# 10_10.net
KiCad netlist of a schematic drawn in EasyEDA Pro
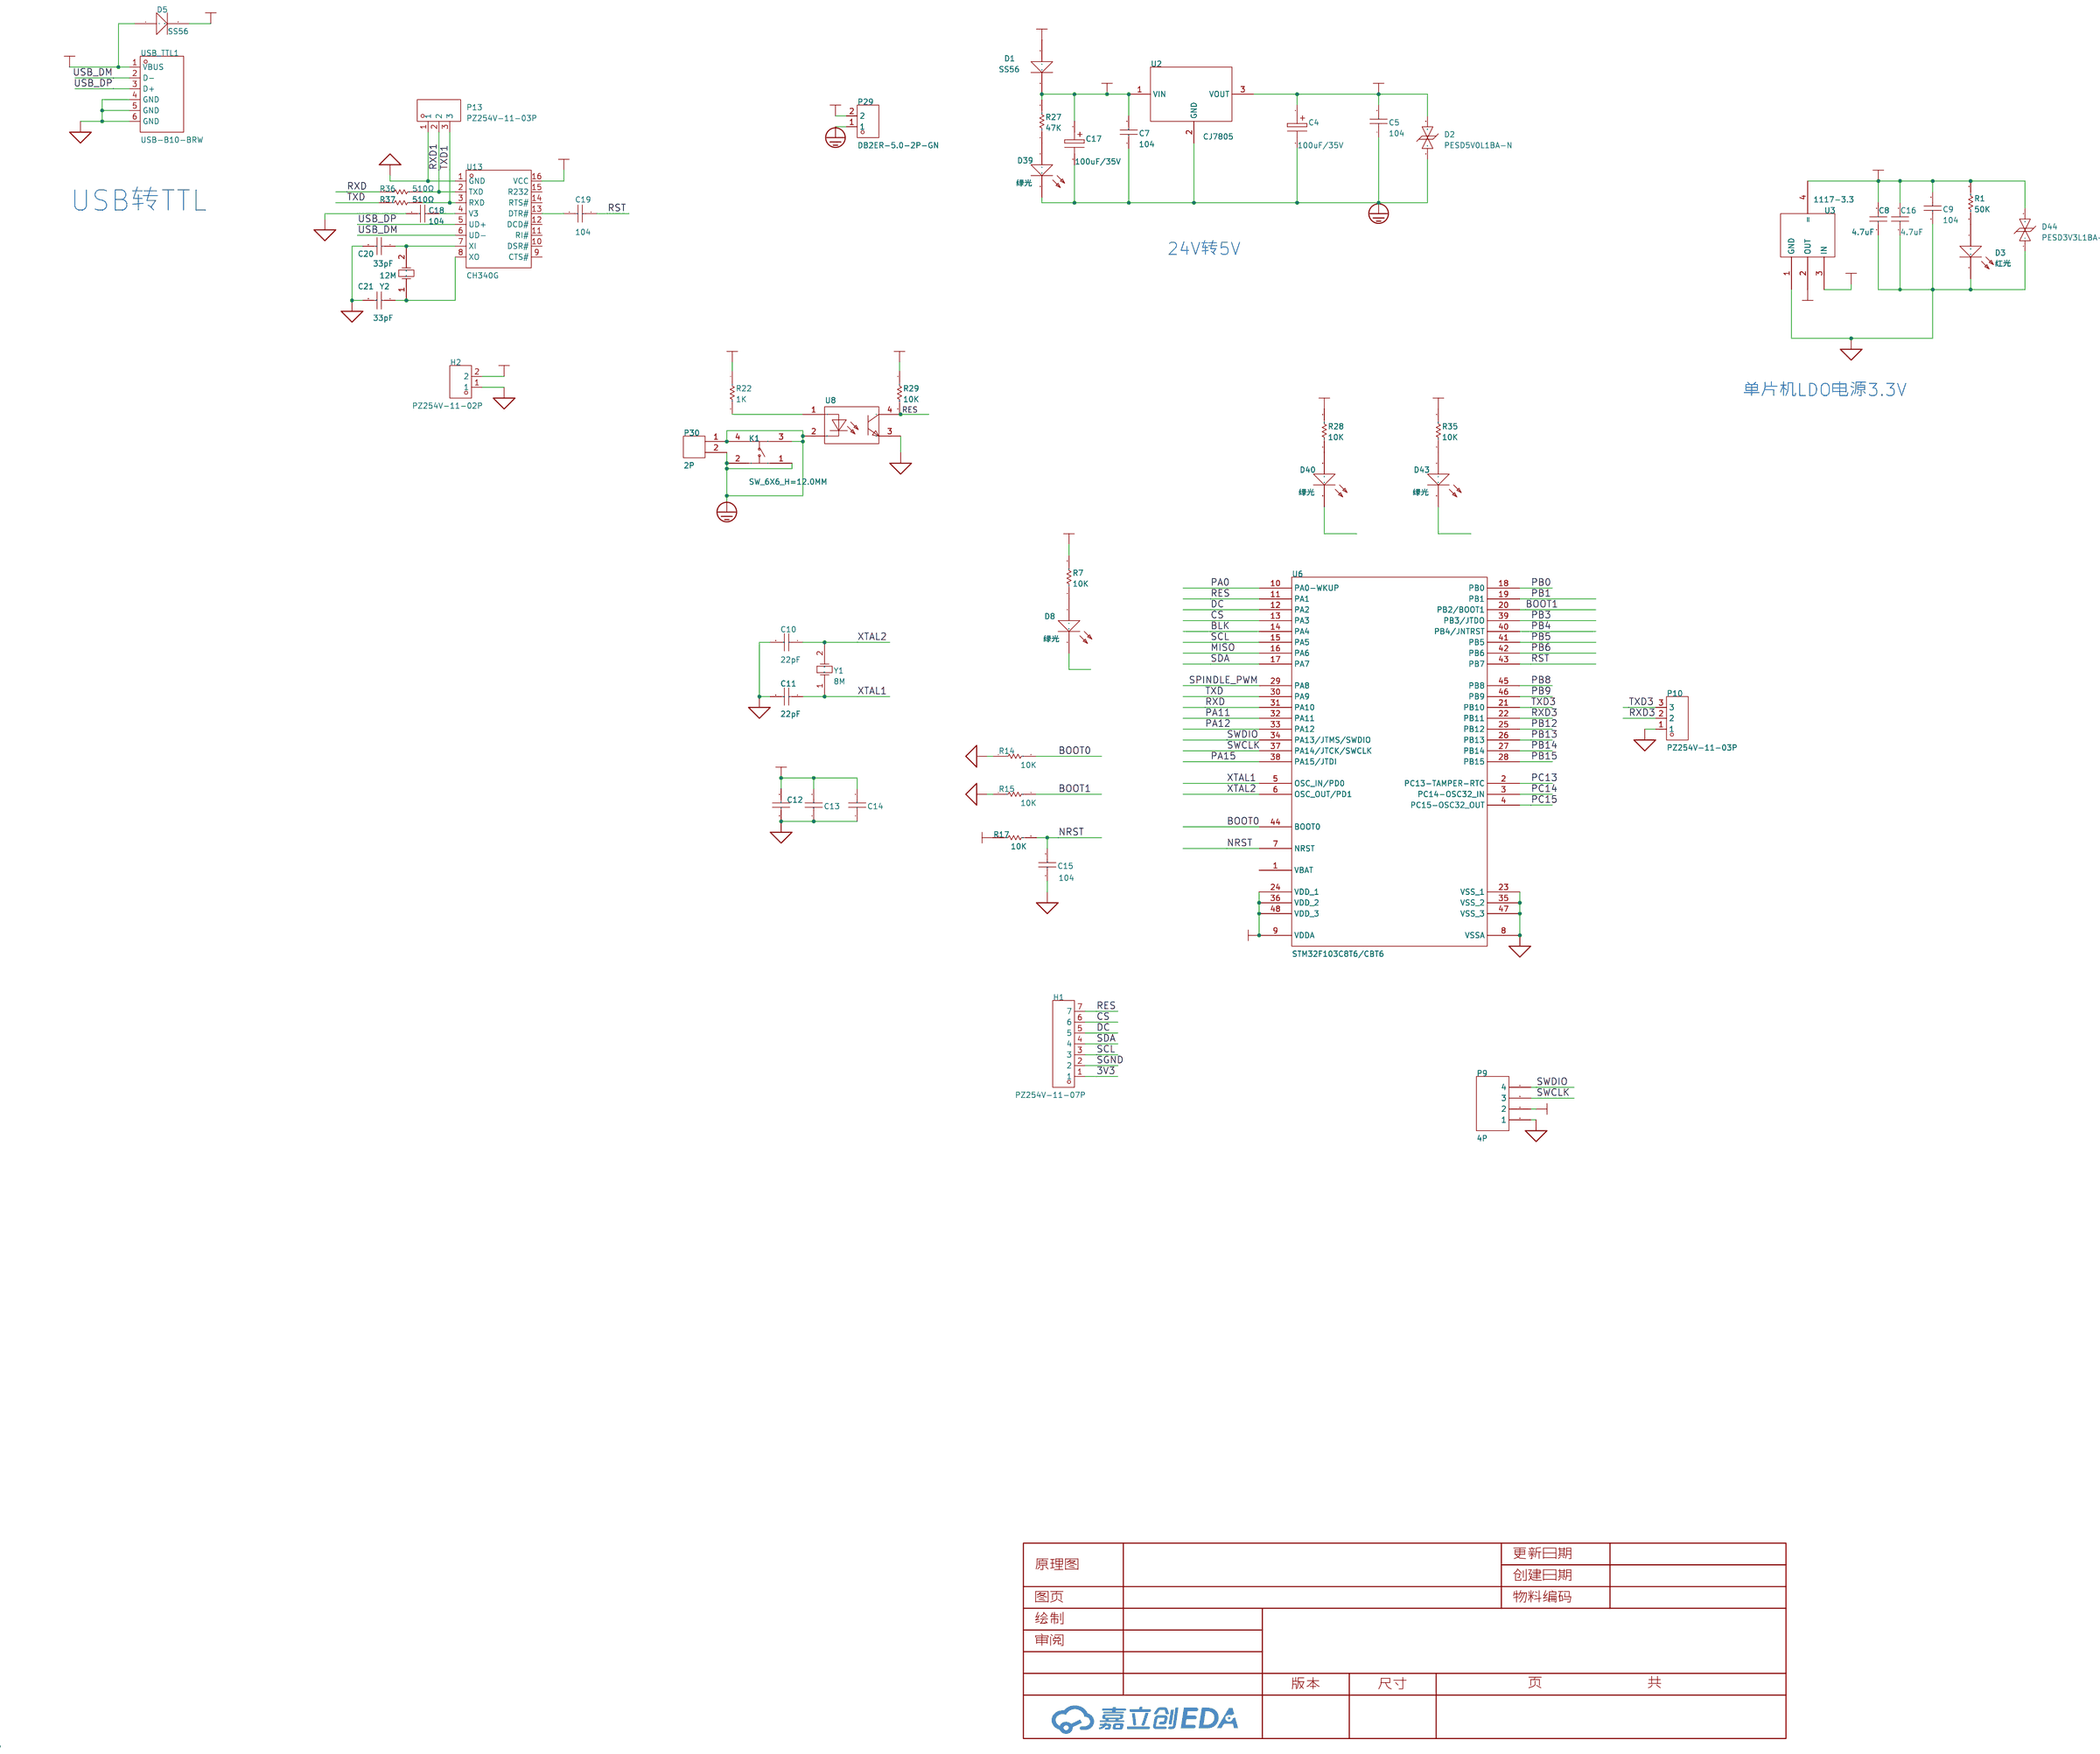
[diagram p0: 主控MCU]
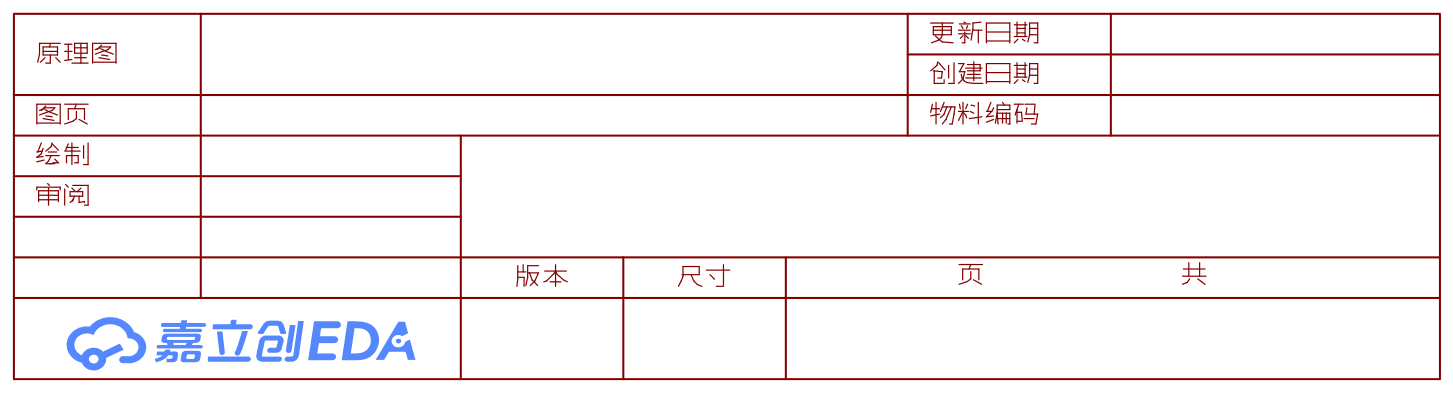
[diagram p1: 电源及控制]

(export (version "E")
  (design (tool "Eeschema 10.0.6"))
  (components
    (comp (ref "C4")
      (value "100uF/35V")
      (footprint "easyedapro:0603C")
      (libsource (lib "easyedapro") (part "ELECTRO1"))
    )
    (comp (ref "C5")
      (value "104")
      (footprint "easyedapro:0603C")
      (description "Capacitor (Semiconductor SIM Model)")
      (libsource (lib "easyedapro") (part "Cap Semi"))
    )
    (comp (ref "C7")
      (value "104")
      (footprint "easyedapro:0603C")
      (description "Capacitor (Semiconductor SIM Model)")
      (libsource (lib "easyedapro") (part "Cap Semi"))
    )
    (comp (ref "C8") (value "4.7uF") (libsource (lib "") (part "CAP_1")))
    (comp (ref "C9")
      (value "104")
      (footprint "easyedapro:0603C")
      (description "Capacitor (Semiconductor SIM Model)")
      (libsource (lib "easyedapro") (part "Cap Semi"))
    )
    (comp (ref "C10")
      (value "100pF")
      (footprint "easyedapro:0603C")
      (description "Capacitor (Semiconductor SIM Model)")
      (libsource (lib "easyedapro") (part "Cap Semi"))
    )
    (comp (ref "C11")
      (value "100pF")
      (footprint "easyedapro:0603C")
      (description "Capacitor (Semiconductor SIM Model)")
      (libsource (lib "easyedapro") (part "Cap Semi"))
    )
    (comp (ref "C12")
      (value "104")
      (footprint "easyedapro:电解电容贴片6X6")
      (libsource (lib "easyedapro") (part "CAP"))
    )
    (comp (ref "C13")
      (value "104")
      (footprint "easyedapro:电解电容贴片6X6")
      (libsource (lib "easyedapro") (part "CAP"))
    )
    (comp (ref "C14")
      (value "104")
      (footprint "easyedapro:电解电容贴片6X6")
      (libsource (lib "easyedapro") (part "CAP"))
    )
    (comp (ref "C15")
      (value "104")
      (footprint "easyedapro:0603C")
      (description "Capacitor (Semiconductor SIM Model)")
      (libsource (lib "easyedapro") (part "Cap Semi"))
    )
    (comp (ref "C16") (value "4.7uF") (libsource (lib "") (part "CAP_1")))
    (comp (ref "C17")
      (value "100uF/35V")
      (footprint "easyedapro:0603C")
      (libsource (lib "easyedapro") (part "ELECTRO1"))
    )
    (comp (ref "C18")
      (value "104")
      (footprint "easyedapro:0603C")
      (description "Capacitor (Semiconductor SIM Model)")
      (libsource (lib "easyedapro") (part "Cap Semi"))
    )
    (comp (ref "C19")
      (value "104")
      (footprint "easyedapro:0603C")
      (description "Capacitor (Semiconductor SIM Model)")
      (libsource (lib "easyedapro") (part "Cap Semi"))
    )
    (comp (ref "C20")
      (value "18pF")
      (footprint "easyedapro:0603C")
      (description "Capacitor (Semiconductor SIM Model)")
      (libsource (lib "easyedapro") (part "Cap Semi"))
    )
    (comp (ref "C21")
      (value "18pF")
      (footprint "easyedapro:0603C")
      (description "Capacitor (Semiconductor SIM Model)")
      (libsource (lib "easyedapro") (part "Cap Semi"))
    )
    (comp (ref "D1")
      (value "SS56")
      (footprint "easyedapro:SMA")
      (libsource (lib "easyedapro") (part "1N4148"))
    )
    (comp (ref "D2")
      (value "PESD5V0L1BA-N")
      (footprint "easyedapro:SOD-523_L1.2-W0.8-LS1.6-BI")
      (description "极性:Bidirectional;反向关断电压（典型值）:5V (Max);击穿电压（最小值）:6V;箝位电压:15V;峰值脉冲电流（10/1000us）:5A (8/20us);")
      (fields (field (name "Manufacturer") "BORN伯恩半导体"))
      (libsource (lib "easyedapro") (part "PESD5V0S1BBN"))
    )
    (comp (ref "D3")
      (value "红光")
      (footprint "easyedapro:0603LED")
      (libsource (lib "easyedapro") (part "LED"))
    )
    (comp (ref "D5")
      (value "SS56")
      (footprint "easyedapro:SMA")
      (libsource (lib "easyedapro") (part "1N4148"))
    )
    (comp (ref "D8")
      (value "绿光")
      (footprint "easyedapro:0603LED")
      (libsource (lib "easyedapro") (part "LED"))
    )
    (comp (ref "D39")
      (value "绿光")
      (footprint "easyedapro:0603LED")
      (libsource (lib "easyedapro") (part "LED"))
    )
    (comp (ref "D40")
      (value "绿光")
      (footprint "easyedapro:0603LED")
      (libsource (lib "easyedapro") (part "LED"))
    )
    (comp (ref "D43")
      (value "绿光")
      (footprint "easyedapro:0603LED")
      (libsource (lib "easyedapro") (part "LED"))
    )
    (comp (ref "D44")
      (value "PESD3V3L1BA-N")
      (footprint "easyedapro:SOD-523_L1.2-W0.8-LS1.6-BI")
      (description "极性:Bidirectional;反向关断电压（典型值）:5V (Max);击穿电压（最小值）:6V;箝位电压:15V;峰值脉冲电流（10/1000us）:5A (8/20us);")
      (fields (field (name "Manufacturer") "BORN伯恩半导体"))
      (libsource (lib "easyedapro") (part "PESD5V0S1BBN"))
    )
    (comp (ref "H1")
      (value "PZ254V-11-07P")
      (footprint "easyedapro:HDR-TH_7P-P2.54-V-M")
      (fields (field (name "Manufacturer") "XFCN(兴飞)"))
      (libsource (lib "easyedapro") (part "PZ254V-11-07P"))
    )
    (comp (ref "H2")
      (value "PZ254V-11-02P")
      (footprint "easyedapro:HDR-TH_2P-P2.54-V-M")
      (fields (field (name "Manufacturer") "XFCN(兴飞)"))
      (libsource (lib "easyedapro") (part "PZ254V-11-02P"))
    )
    (comp (ref "K1")
      (value "SW_6X6_H=12.0MM")
      (footprint "easyedapro:KEY-SMD_4P-L6.0-W6.0-P4.50-LS9.0")
      (libsource (lib "easyedapro") (part "SW_6X6_H=12.0MM"))
    )
    (comp (ref "P9") (value "4P") (libsource (lib "easyedapro") (part "4P")))
    (comp (ref "P10")
      (value "PZ254V-11-03P")
      (footprint "easyedapro:HDR-TH_3P-P2.54-V-M")
      (fields (field (name "Manufacturer") "XFCN(兴飞)"))
      (libsource (lib "easyedapro") (part "PZ254V-11-03P_C2937625"))
    )
    (comp (ref "P13")
      (value "PZ254V-11-03P")
      (footprint "easyedapro:HDR-TH_3P-P2.54-V-M")
      (fields (field (name "Manufacturer") "XFCN(兴飞)"))
      (libsource (lib "easyedapro") (part "PZ254V-11-03P_C2937625"))
    )
    (comp (ref "P29")
      (value "DB2ER-5.0-2P-GN")
      (footprint "easyedapro:CONN-TH_2P-P5.00_DB2ER-5.0-2P-GN")
      (description "间距:5mm;颜色:绿色;排数:1;每排PIN数:2;额定电流:15A;额定电压:630V;触头镀层:锡;")
      (fields (field (name "Manufacturer") "DORABO(地博电气)"))
      (libsource (lib "easyedapro") (part "DB2ER-5.0-2P-GN"))
    )
    (comp (ref "P30") (value "2P") (libsource (lib "easyedapro") (part "2P")))
    (comp (ref "R1")
      (value "50K")
      (footprint "easyedapro:0603R")
      (description "Resistor")
      (libsource (lib "easyedapro") (part "RES"))
    )
    (comp (ref "R7")
      (value "10K")
      (footprint "easyedapro:0603R")
      (description "Resistor")
      (libsource (lib "easyedapro") (part "RES"))
    )
    (comp (ref "R14")
      (value "10K")
      (footprint "easyedapro:0603R")
      (description "Resistor")
      (libsource (lib "easyedapro") (part "RES"))
    )
    (comp (ref "R15")
      (value "10K")
      (footprint "easyedapro:0603R")
      (description "Resistor")
      (libsource (lib "easyedapro") (part "RES"))
    )
    (comp (ref "R17")
      (value "10K")
      (footprint "easyedapro:0603R")
      (description "Resistor")
      (libsource (lib "easyedapro") (part "RES"))
    )
    (comp (ref "R22")
      (value "1K")
      (footprint "easyedapro:0603R")
      (description "Resistor")
      (libsource (lib "easyedapro") (part "RES"))
    )
    (comp (ref "R27")
      (value "47K")
      (footprint "easyedapro:0603R")
      (description "Resistor")
      (libsource (lib "easyedapro") (part "RES"))
    )
    (comp (ref "R28")
      (value "10K")
      (footprint "easyedapro:0603R")
      (description "Resistor")
      (libsource (lib "easyedapro") (part "RES"))
    )
    (comp (ref "R29")
      (value "10K")
      (footprint "easyedapro:0603R")
      (description "Resistor")
      (libsource (lib "easyedapro") (part "RES"))
    )
    (comp (ref "R35")
      (value "10K")
      (footprint "easyedapro:0603R")
      (description "Resistor")
      (libsource (lib "easyedapro") (part "RES"))
    )
    (comp (ref "R36")
      (value "510Ω")
      (footprint "easyedapro:0603R")
      (description "Resistor")
      (libsource (lib "easyedapro") (part "RES"))
    )
    (comp (ref "R37")
      (value "510Ω")
      (footprint "easyedapro:0603R")
      (description "Resistor")
      (libsource (lib "easyedapro") (part "RES"))
    )
    (comp (ref "U2")
      (value "CJ7805")
      (footprint "easyedapro:TO-263-2")
      (libsource (lib "easyedapro") (part "7805"))
    )
    (comp (ref "U3")
      (value "1117-3.3")
      (footprint "easyedapro:SOT-223")
      (libsource (lib "easyedapro") (part "LM1117"))
    )
    (comp (ref "U6")
      (value "STM32F103C8T6/CBT6")
      (footprint "easyedapro:LQFP48")
      (description "STM32 ARM-based 32-bit MCU with 32 Kbytes Flash, 48-pin LQFP, Industrial Temperature")
      (libsource (lib "easyedapro") (part "STM32F103C6T6"))
    )
    (comp (ref "U8")
      (value "LTV-357T-C")
      (footprint "easyedapro:SOP-4_L4.4-W3.9-P2.54-LS7.0-TL")
      (fields (field (name "Manufacturer") "LITEON(光宝)"))
      (libsource (lib "easyedapro") (part "LTV-357T-C"))
    )
    (comp (ref "U13")
      (value "CH340G")
      (footprint "easyedapro:SOIC-16_L9.9-W3.9-P1.27-LS6.0-BL")
      (description "应用功能:收发器;接口协议:USB 2.0;数据速率:2Mbps;")
      (fields (field (name "Manufacturer") "WCH(南京沁恒)"))
      (libsource (lib "easyedapro") (part "CH340G"))
    )
    (comp (ref "USB_TTL1")
      (value "USB-B10-BRW")
      (footprint "easyedapro:USB-B-TH_USB-B10-BRW")
      (fields (field (name "Manufacturer") "XUNPU(讯普)"))
      (libsource (lib "easyedapro") (part "USB-B10-BRW"))
    )
    (comp (ref "Y1")
      (value "8M")
      (footprint "easyedapro:晶振贴片49SSMD")
      (description "Crystal Oscillator")
      (libsource (lib "easyedapro") (part "XTAL"))
    )
    (comp (ref "Y2")
      (value "12M")
      (footprint "easyedapro:晶振贴片49SSMD")
      (description "Crystal Oscillator")
      (libsource (lib "easyedapro") (part "XTAL"))
    )
  )
  (nets
    (net (code "1") (name "3V3") (class "Default")
      (node (ref "C12") (pin "2") (pinfunction "2_2") (pintype "unspecified"))
      (node (ref "C13") (pin "2") (pinfunction "2_2") (pintype "unspecified"))
      (node (ref "C14") (pin "2") (pinfunction "2_2") (pintype "unspecified"))
      (node (ref "C16") (pin "2") (pinfunction "2_2") (pintype "input"))
      (node (ref "C8") (pin "2") (pinfunction "2_2") (pintype "input"))
      (node (ref "C9") (pin "2") (pinfunction "2_2") (pintype "unspecified"))
      (node (ref "D44") (pin "2") (pinfunction "2_2") (pintype "input"))
      (node (ref "H1") (pin "1") (pinfunction "1_1") (pintype "unspecified"))
      (node (ref "P9") (pin "2") (pinfunction "2_2") (pintype "input"))
      (node (ref "R1") (pin "1") (pinfunction "1_1") (pintype "unspecified"))
      (node (ref "R17") (pin "1") (pinfunction "1_1") (pintype "unspecified"))
      (node (ref "R28") (pin "2") (pinfunction "2_2") (pintype "unspecified"))
      (node (ref "R29") (pin "1") (pinfunction "1_1") (pintype "unspecified"))
      (node (ref "R35") (pin "2") (pinfunction "2_2") (pintype "unspecified"))
      (node (ref "R7") (pin "2") (pinfunction "2_2") (pintype "unspecified"))
      (node (ref "U3") (pin "2") (pinfunction "OUT_2") (pintype "unspecified"))
      (node (ref "U3") (pin "4") (pinfunction "=_4") (pintype "unspecified"))
      (node (ref "U6") (pin "24") (pinfunction "VDD_1_24") (pintype "unspecified"))
      (node (ref "U6") (pin "36") (pinfunction "VDD_2_36") (pintype "unspecified"))
      (node (ref "U6") (pin "48") (pinfunction "VDD_3_48") (pintype "unspecified"))
      (node (ref "U6") (pin "9") (pinfunction "VDDA_9") (pintype "unspecified"))
    )
    (net (code "2") (name "5V_VCC") (class "Default")
      (node (ref "C4") (pin "1") (pintype "unspecified"))
      (node (ref "C5") (pin "2") (pinfunction "2_2") (pintype "unspecified"))
      (node (ref "D2") (pin "2") (pinfunction "2_2") (pintype "input"))
      (node (ref "D5") (pin "2") (pinfunction "2_2") (pintype "unspecified"))
      (node (ref "H2") (pin "2") (pinfunction "2_2") (pintype "unspecified"))
      (node (ref "R22") (pin "1") (pinfunction "1_1") (pintype "unspecified"))
      (node (ref "U13") (pin "16") (pinfunction "VCC_16") (pintype "unspecified"))
      (node (ref "U2") (pin "3") (pinfunction "VOUT_3") (pintype "unspecified"))
      (node (ref "U3") (pin "3") (pinfunction "IN_3") (pintype "unspecified"))
    )
    (net (code "3") (name "24V") (class "Default")
      (node (ref "D1") (pin "1") (pinfunction "1_1") (pintype "unspecified"))
      (node (ref "P29") (pin "2") (pinfunction "2_2") (pintype "unspecified"))
    )
    (net (code "4") (name "BLK") (class "Default")
      (node (ref "U6") (pin "14") (pinfunction "PA4_14") (pintype "bidirectional"))
    )
    (net (code "5") (name "BOOT0") (class "Default")
      (node (ref "R14") (pin "2") (pinfunction "2_2") (pintype "unspecified"))
      (node (ref "U6") (pin "44") (pinfunction "BOOT0_44") (pintype "input"))
    )
    (net (code "6") (name "BOOT1") (class "Default")
      (node (ref "R15") (pin "2") (pinfunction "2_2") (pintype "unspecified"))
      (node (ref "U6") (pin "20") (pinfunction "PB2/BOOT1_20") (pintype "bidirectional"))
    )
    (net (code "7") (name "CS") (class "Default")
      (node (ref "H1") (pin "6") (pinfunction "6_6") (pintype "unspecified"))
      (node (ref "U6") (pin "13") (pinfunction "PA3_13") (pintype "bidirectional"))
    )
    (net (code "8") (name "DC") (class "Default")
      (node (ref "H1") (pin "5") (pinfunction "5_5") (pintype "unspecified"))
      (node (ref "U6") (pin "12") (pinfunction "PA2_12") (pintype "bidirectional"))
    )
    (net (code "9") (name "MISO") (class "Default")
      (node (ref "U6") (pin "16") (pinfunction "PA6_16") (pintype "bidirectional"))
    )
    (net (code "10") (name "NRST") (class "Default")
      (node (ref "C15") (pin "2") (pinfunction "2_2") (pintype "unspecified"))
      (node (ref "R17") (pin "2") (pinfunction "2_2") (pintype "unspecified"))
      (node (ref "U6") (pin "7") (pinfunction "NRST_7") (pintype "bidirectional"))
    )
    (net (code "11") (name "Net-(D3-Pad1)") (class "Default")
      (node (ref "D3") (pin "1") (pinfunction "1_1") (pintype "unspecified"))
      (node (ref "R1") (pin "2") (pinfunction "2_2") (pintype "unspecified"))
    )
    (net (code "12") (name "Net-(D8-Pad1)") (class "Default")
      (node (ref "D8") (pin "1") (pinfunction "1_1") (pintype "unspecified"))
      (node (ref "R7") (pin "1") (pinfunction "1_1") (pintype "unspecified"))
    )
    (net (code "13") (name "Net-(D39-Pad1)") (class "Default")
      (node (ref "D39") (pin "1") (pinfunction "1_1") (pintype "unspecified"))
      (node (ref "R27") (pin "1") (pinfunction "1_1") (pintype "unspecified"))
    )
    (net (code "14") (name "Net-(D40-Pad1)") (class "Default")
      (node (ref "D40") (pin "1") (pinfunction "1_1") (pintype "unspecified"))
      (node (ref "R28") (pin "1") (pinfunction "1_1") (pintype "unspecified"))
    )
    (net (code "15") (name "Net-(D43-Pad1)") (class "Default")
      (node (ref "D43") (pin "1") (pinfunction "1_1") (pintype "unspecified"))
      (node (ref "R35") (pin "1") (pinfunction "1_1") (pintype "unspecified"))
    )
    (net (code "16") (name "Net-(R22-Pad2)") (class "Default")
      (node (ref "R22") (pin "2") (pinfunction "2_2") (pintype "unspecified"))
      (node (ref "U8") (pin "1") (pinfunction "1_1") (pintype "unspecified"))
    )
    (net (code "17") (name "Net-(U13-DTR#)") (class "Default")
      (node (ref "C19") (pin "1") (pinfunction "1_1") (pintype "unspecified"))
      (node (ref "U13") (pin "13") (pinfunction "DTR#_13") (pintype "unspecified"))
    )
    (net (code "18") (name "Net-(U13-V3)") (class "Default")
      (node (ref "C18") (pin "1") (pinfunction "1_1") (pintype "unspecified"))
      (node (ref "U13") (pin "4") (pinfunction "V3_4") (pintype "unspecified"))
    )
    (net (code "19") (name "Net-(U13-XI)") (class "Default")
      (node (ref "C20") (pin "1") (pinfunction "1_1") (pintype "unspecified"))
      (node (ref "U13") (pin "7") (pinfunction "XI_7") (pintype "unspecified"))
      (node (ref "Y2") (pin "2") (pinfunction "OSC2_2") (pintype "unspecified"))
    )
    (net (code "20") (name "Net-(U13-XO)") (class "Default")
      (node (ref "C21") (pin "1") (pinfunction "1_1") (pintype "unspecified"))
      (node (ref "U13") (pin "8") (pinfunction "XO_8") (pintype "unspecified"))
      (node (ref "Y2") (pin "1") (pinfunction "OSC1_1") (pintype "unspecified"))
    )
    (net (code "21") (name "PA0") (class "Default")
      (node (ref "U6") (pin "10") (pinfunction "PA0-WKUP_10") (pintype "bidirectional"))
    )
    (net (code "22") (name "PA11") (class "Default")
      (node (ref "U6") (pin "32") (pinfunction "PA11_32") (pintype "bidirectional"))
    )
    (net (code "23") (name "PA12") (class "Default")
      (node (ref "U6") (pin "33") (pinfunction "PA12_33") (pintype "bidirectional"))
    )
    (net (code "24") (name "PA15") (class "Default")
      (node (ref "U6") (pin "38") (pinfunction "PA15/JTDI_38") (pintype "bidirectional"))
    )
    (net (code "25") (name "PB0") (class "Default")
      (node (ref "U6") (pin "18") (pinfunction "PB0_18") (pintype "bidirectional"))
    )
    (net (code "26") (name "PB1") (class "Default")
      (node (ref "U6") (pin "19") (pinfunction "PB1_19") (pintype "bidirectional"))
    )
    (net (code "27") (name "PB3") (class "Default")
      (node (ref "U6") (pin "39") (pinfunction "PB3/JTDO_39") (pintype "bidirectional"))
    )
    (net (code "28") (name "PB4") (class "Default")
      (node (ref "U6") (pin "40") (pinfunction "PB4/JNTRST_40") (pintype "bidirectional"))
    )
    (net (code "29") (name "PB5") (class "Default")
      (node (ref "U6") (pin "41") (pinfunction "PB5_41") (pintype "bidirectional"))
    )
    (net (code "30") (name "PB6") (class "Default")
      (node (ref "U6") (pin "42") (pinfunction "PB6_42") (pintype "bidirectional"))
    )
    (net (code "31") (name "PB8") (class "Default")
      (node (ref "U6") (pin "45") (pinfunction "PB8_45") (pintype "bidirectional"))
    )
    (net (code "32") (name "PB9") (class "Default")
      (node (ref "U6") (pin "46") (pinfunction "PB9_46") (pintype "bidirectional"))
    )
    (net (code "33") (name "PB12") (class "Default")
      (node (ref "U6") (pin "25") (pinfunction "PB12_25") (pintype "bidirectional"))
    )
    (net (code "34") (name "PB13") (class "Default")
      (node (ref "U6") (pin "26") (pinfunction "PB13_26") (pintype "bidirectional"))
    )
    (net (code "35") (name "PB14") (class "Default")
      (node (ref "U6") (pin "27") (pinfunction "PB14_27") (pintype "bidirectional"))
    )
    (net (code "36") (name "PB15") (class "Default")
      (node (ref "U6") (pin "28") (pinfunction "PB15_28") (pintype "bidirectional"))
    )
    (net (code "37") (name "PC13") (class "Default")
      (node (ref "U6") (pin "2") (pinfunction "PC13-TAMPER-RTC_2") (pintype "bidirectional"))
    )
    (net (code "38") (name "PC14") (class "Default")
      (node (ref "U6") (pin "3") (pinfunction "PC14-OSC32_IN_3") (pintype "bidirectional"))
    )
    (net (code "39") (name "PC15") (class "Default")
      (node (ref "U6") (pin "4") (pinfunction "PC15-OSC32_OUT_4") (pintype "bidirectional"))
    )
    (net (code "40") (name "RES") (class "Default")
      (node (ref "H1") (pin "7") (pinfunction "7_7") (pintype "unspecified"))
      (node (ref "R29") (pin "2") (pinfunction "2_2") (pintype "unspecified"))
      (node (ref "U6") (pin "11") (pinfunction "PA1_11") (pintype "bidirectional"))
      (node (ref "U8") (pin "4") (pinfunction "4_4") (pintype "unspecified"))
    )
    (net (code "41") (name "RST") (class "Default")
      (node (ref "C19") (pin "2") (pinfunction "2_2") (pintype "unspecified"))
      (node (ref "U6") (pin "43") (pinfunction "PB7_43") (pintype "bidirectional"))
    )
    (net (code "42") (name "RXD") (class "Default")
      (node (ref "R36") (pin "2") (pinfunction "2_2") (pintype "unspecified"))
      (node (ref "U6") (pin "31") (pinfunction "PA10_31") (pintype "bidirectional"))
    )
    (net (code "43") (name "RXD1") (class "Default")
      (node (ref "P13") (pin "2") (pinfunction "2_2") (pintype "unspecified"))
      (node (ref "R36") (pin "1") (pinfunction "1_1") (pintype "unspecified"))
      (node (ref "U13") (pin "2") (pinfunction "TXD_2") (pintype "unspecified"))
    )
    (net (code "44") (name "RXD3") (class "Default")
      (node (ref "P10") (pin "2") (pinfunction "2_2") (pintype "unspecified"))
      (node (ref "U6") (pin "22") (pinfunction "PB11_22") (pintype "bidirectional"))
    )
    (net (code "45") (name "SCL") (class "Default")
      (node (ref "H1") (pin "3") (pinfunction "3_3") (pintype "unspecified"))
      (node (ref "U6") (pin "15") (pinfunction "PA5_15") (pintype "bidirectional"))
    )
    (net (code "46") (name "SDA") (class "Default")
      (node (ref "H1") (pin "4") (pinfunction "4_4") (pintype "unspecified"))
      (node (ref "U6") (pin "17") (pinfunction "PA7_17") (pintype "bidirectional"))
    )
    (net (code "47") (name "SGND") (class "Default")
      (node (ref "C10") (pin "2") (pinfunction "2_2") (pintype "unspecified"))
      (node (ref "C11") (pin "2") (pinfunction "2_2") (pintype "unspecified"))
      (node (ref "C12") (pin "1") (pinfunction "1_1") (pintype "unspecified"))
      (node (ref "C13") (pin "1") (pinfunction "1_1") (pintype "unspecified"))
      (node (ref "C14") (pin "1") (pinfunction "1_1") (pintype "unspecified"))
      (node (ref "C15") (pin "1") (pinfunction "1_1") (pintype "unspecified"))
      (node (ref "C16") (pin "1") (pinfunction "1_1") (pintype "input"))
      (node (ref "C17") (pin "2") (pintype "unspecified"))
      (node (ref "C18") (pin "2") (pinfunction "2_2") (pintype "unspecified"))
      (node (ref "C20") (pin "2") (pinfunction "2_2") (pintype "unspecified"))
      (node (ref "C21") (pin "2") (pinfunction "2_2") (pintype "unspecified"))
      (node (ref "C4") (pin "2") (pintype "unspecified"))
      (node (ref "C5") (pin "1") (pinfunction "1_1") (pintype "unspecified"))
      (node (ref "C7") (pin "1") (pinfunction "1_1") (pintype "unspecified"))
      (node (ref "C8") (pin "1") (pinfunction "1_1") (pintype "input"))
      (node (ref "C9") (pin "1") (pinfunction "1_1") (pintype "unspecified"))
      (node (ref "D2") (pin "1") (pinfunction "1_1") (pintype "input"))
      (node (ref "D3") (pin "2") (pinfunction "2_2") (pintype "unspecified"))
      (node (ref "D39") (pin "2") (pinfunction "2_2") (pintype "unspecified"))
      (node (ref "D44") (pin "1") (pinfunction "1_1") (pintype "input"))
      (node (ref "H1") (pin "2") (pinfunction "2_2") (pintype "unspecified"))
      (node (ref "H2") (pin "1") (pinfunction "1_1") (pintype "unspecified"))
      (node (ref "K1") (pin "1") (pinfunction "1_1") (pintype "unspecified"))
      (node (ref "K1") (pin "2") (pinfunction "2_2") (pintype "unspecified"))
      (node (ref "K1") (pin "3") (pinfunction "3_3") (pintype "unspecified"))
      (node (ref "K1") (pin "4") (pinfunction "4_4") (pintype "unspecified"))
      (node (ref "P10") (pin "1") (pinfunction "1_1") (pintype "unspecified"))
      (node (ref "P13") (pin "1") (pinfunction "1_1") (pintype "unspecified"))
      (node (ref "P29") (pin "1") (pinfunction "1_1") (pintype "unspecified"))
      (node (ref "P30") (pin "1") (pintype "input"))
      (node (ref "P30") (pin "2") (pintype "input"))
      (node (ref "P9") (pin "1") (pinfunction "1_1") (pintype "input"))
      (node (ref "R14") (pin "1") (pinfunction "1_1") (pintype "unspecified"))
      (node (ref "R15") (pin "1") (pinfunction "1_1") (pintype "unspecified"))
      (node (ref "U13") (pin "1") (pinfunction "GND_1") (pintype "unspecified"))
      (node (ref "U2") (pin "2") (pinfunction "GND_2") (pintype "unspecified"))
      (node (ref "U3") (pin "1") (pinfunction "GND_1") (pintype "unspecified"))
      (node (ref "U6") (pin "23") (pinfunction "VSS_1_23") (pintype "unspecified"))
      (node (ref "U6") (pin "35") (pinfunction "VSS_2_35") (pintype "unspecified"))
      (node (ref "U6") (pin "47") (pinfunction "VSS_3_47") (pintype "unspecified"))
      (node (ref "U6") (pin "8") (pinfunction "VSSA_8") (pintype "unspecified"))
      (node (ref "U8") (pin "2") (pinfunction "2_2") (pintype "unspecified"))
      (node (ref "U8") (pin "3") (pinfunction "3_3") (pintype "unspecified"))
      (node (ref "USB_TTL1") (pin "4") (pinfunction "GND_4") (pintype "unspecified"))
      (node (ref "USB_TTL1") (pin "5") (pinfunction "GND_5") (pintype "unspecified"))
      (node (ref "USB_TTL1") (pin "6") (pinfunction "GND_6") (pintype "unspecified"))
    )
    (net (code "48") (name "SPINDLE_PWM") (class "Default")
      (node (ref "U6") (pin "29") (pinfunction "PA8_29") (pintype "bidirectional"))
    )
    (net (code "49") (name "SWCLK") (class "Default")
      (node (ref "P9") (pin "3") (pinfunction "3_3") (pintype "input"))
      (node (ref "U6") (pin "37") (pinfunction "PA14/JTCK/SWCLK_37") (pintype "bidirectional"))
    )
    (net (code "50") (name "SWDIO") (class "Default")
      (node (ref "P9") (pin "4") (pinfunction "4_4") (pintype "input"))
      (node (ref "U6") (pin "34") (pinfunction "PA13/JTMS/SWDIO_34") (pintype "bidirectional"))
    )
    (net (code "51") (name "TXD") (class "Default")
      (node (ref "R37") (pin "2") (pinfunction "2_2") (pintype "unspecified"))
      (node (ref "U6") (pin "30") (pinfunction "PA9_30") (pintype "bidirectional"))
    )
    (net (code "52") (name "TXD1") (class "Default")
      (node (ref "P13") (pin "3") (pinfunction "3_3") (pintype "unspecified"))
      (node (ref "R37") (pin "1") (pinfunction "1_1") (pintype "unspecified"))
      (node (ref "U13") (pin "3") (pinfunction "RXD_3") (pintype "unspecified"))
    )
    (net (code "53") (name "TXD3") (class "Default")
      (node (ref "P10") (pin "3") (pinfunction "3_3") (pintype "unspecified"))
      (node (ref "U6") (pin "21") (pinfunction "PB10_21") (pintype "bidirectional"))
    )
    (net (code "54") (name "USB_DM") (class "Default")
      (node (ref "U13") (pin "6") (pinfunction "UD-_6") (pintype "unspecified"))
      (node (ref "USB_TTL1") (pin "2") (pinfunction "D-_2") (pintype "unspecified"))
    )
    (net (code "55") (name "USB_DP") (class "Default")
      (node (ref "U13") (pin "5") (pinfunction "UD+_5") (pintype "unspecified"))
      (node (ref "USB_TTL1") (pin "3") (pinfunction "D+_3") (pintype "unspecified"))
    )
    (net (code "56") (name "VIN_24V") (class "Default")
      (node (ref "C17") (pin "1") (pintype "unspecified"))
      (node (ref "C7") (pin "2") (pinfunction "2_2") (pintype "unspecified"))
      (node (ref "D1") (pin "2") (pinfunction "2_2") (pintype "unspecified"))
      (node (ref "R27") (pin "2") (pinfunction "2_2") (pintype "unspecified"))
      (node (ref "U2") (pin "1") (pinfunction "VIN_1") (pintype "unspecified"))
    )
    (net (code "57") (name "VUSB") (class "Default")
      (node (ref "D5") (pin "1") (pinfunction "1_1") (pintype "unspecified"))
      (node (ref "USB_TTL1") (pin "1") (pinfunction "VBUS_1") (pintype "unspecified"))
    )
    (net (code "58") (name "XTAL1") (class "Default")
      (node (ref "C11") (pin "1") (pinfunction "1_1") (pintype "unspecified"))
      (node (ref "U6") (pin "5") (pinfunction "OSC_IN/PD0_5") (pintype "input"))
      (node (ref "Y1") (pin "1") (pinfunction "OSC1_1") (pintype "unspecified"))
    )
    (net (code "59") (name "XTAL2") (class "Default")
      (node (ref "C10") (pin "1") (pinfunction "1_1") (pintype "unspecified"))
      (node (ref "U6") (pin "6") (pinfunction "OSC_OUT/PD1_6") (pintype "output"))
      (node (ref "Y1") (pin "2") (pinfunction "OSC2_2") (pintype "unspecified"))
    )
    (net (code "60") (name "unconnected-(D8-Pad2)") (class "Default")
      (node (ref "D8") (pin "2") (pinfunction "2_2") (pintype "unspecified"))
    )
    (net (code "61") (name "unconnected-(D40-Pad2)") (class "Default")
      (node (ref "D40") (pin "2") (pinfunction "2_2") (pintype "unspecified"))
    )
    (net (code "62") (name "unconnected-(D43-Pad2)") (class "Default")
      (node (ref "D43") (pin "2") (pinfunction "2_2") (pintype "unspecified"))
    )
    (net (code "63") (name "unconnected-(U6-VBAT-Pad1)") (class "Default")
      (node (ref "U6") (pin "1") (pinfunction "VBAT_1") (pintype "unspecified"))
    )
    (net (code "64") (name "unconnected-(U13-CTS#-Pad9)") (class "Default")
      (node (ref "U13") (pin "9") (pinfunction "CTS#_9") (pintype "unspecified"))
    )
    (net (code "65") (name "unconnected-(U13-DCD#-Pad12)") (class "Default")
      (node (ref "U13") (pin "12") (pinfunction "DCD#_12") (pintype "unspecified"))
    )
    (net (code "66") (name "unconnected-(U13-DSR#-Pad10)") (class "Default")
      (node (ref "U13") (pin "10") (pinfunction "DSR#_10") (pintype "unspecified"))
    )
    (net (code "67") (name "unconnected-(U13-R232-Pad15)") (class "Default")
      (node (ref "U13") (pin "15") (pinfunction "R232_15") (pintype "unspecified"))
    )
    (net (code "68") (name "unconnected-(U13-RI#-Pad11)") (class "Default")
      (node (ref "U13") (pin "11") (pinfunction "RI#_11") (pintype "unspecified"))
    )
    (net (code "69") (name "unconnected-(U13-RTS#-Pad14)") (class "Default")
      (node (ref "U13") (pin "14") (pinfunction "RTS#_14") (pintype "unspecified"))
    )
  )
)
